# Breakout.net
KiCad netlist of a schematic drawn in Altium Designer
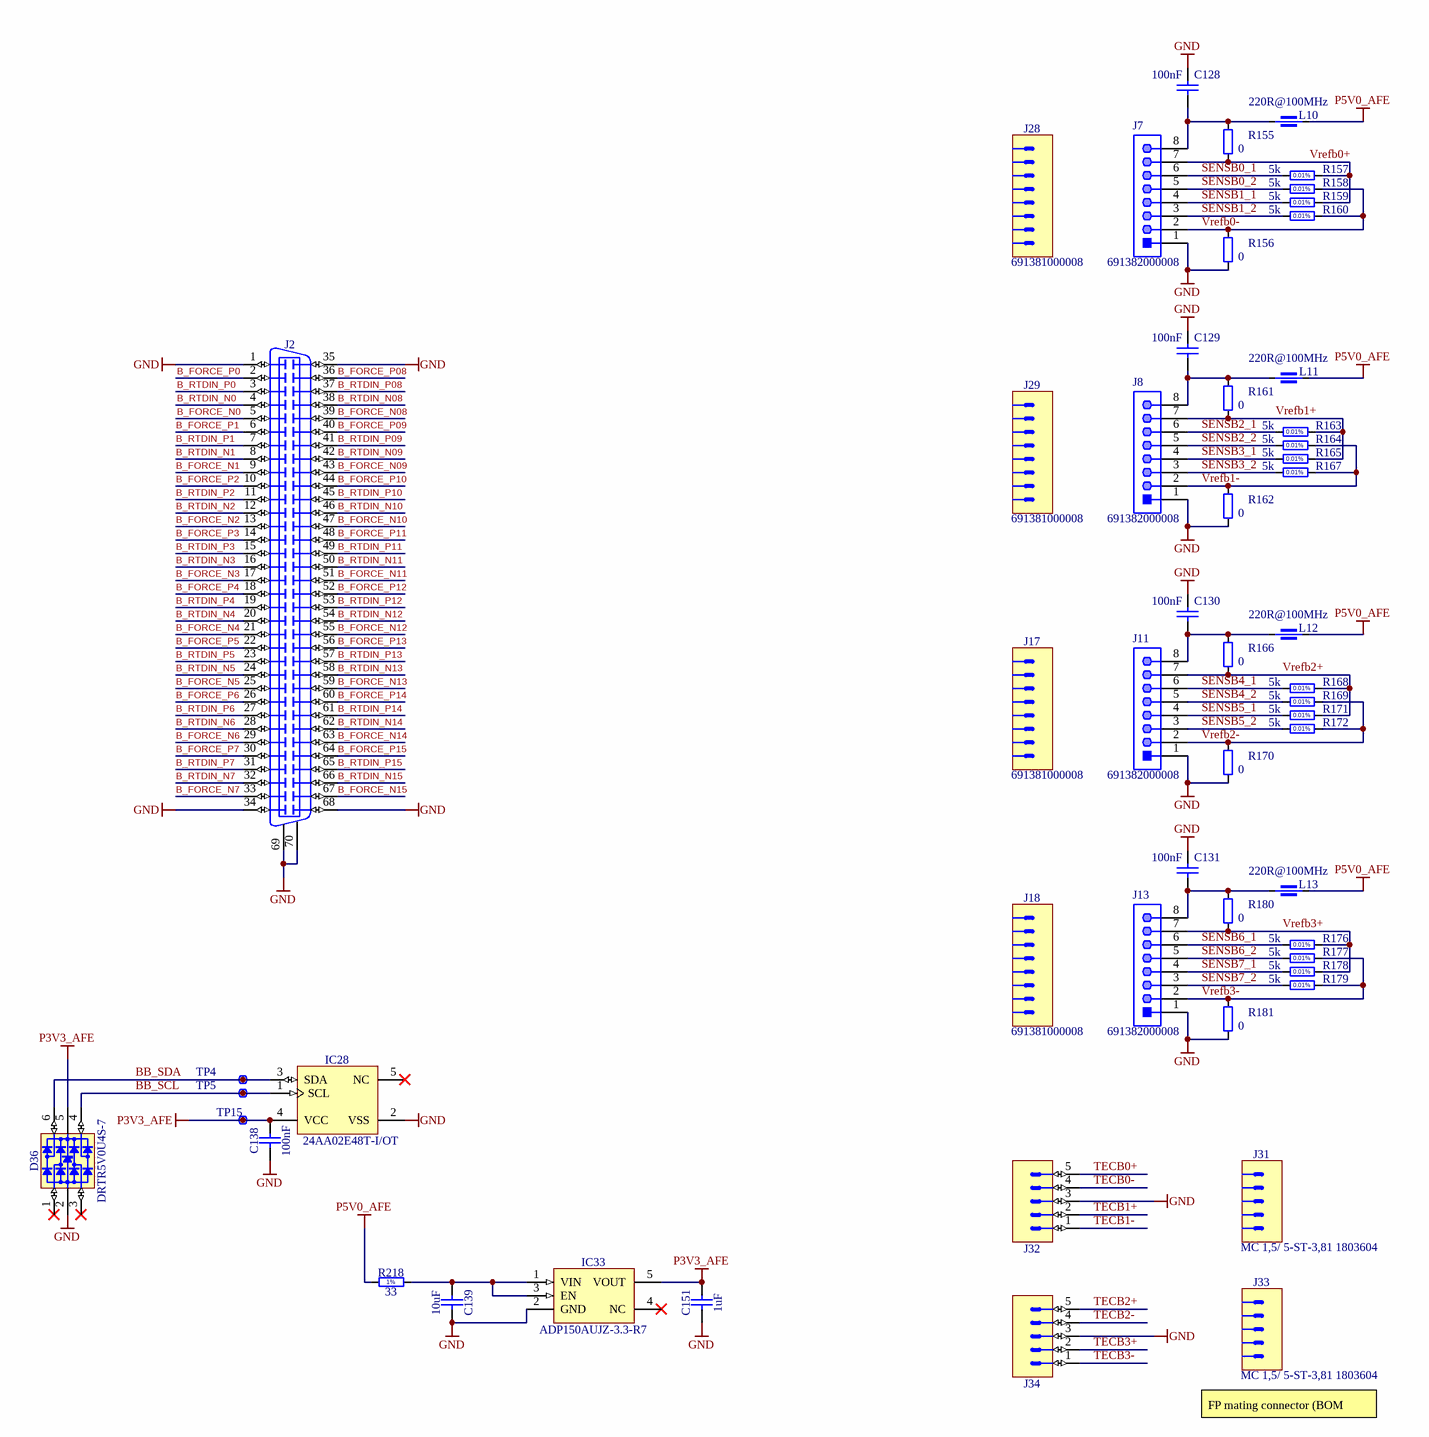
[diagram p0: Breakout.SchDoc]

(export (version "E")
  (design (tool "Eeschema 10.0.6"))
  (components
    (comp (ref "C128")
      (value "100nF")
      (footprint "CAPC1005X55N")
      (description "Non-polarised capacitor")
      (fields
        (field (name "PART NUMBER") "CC0402_100NF_16V_10%_X5R")
        (field (name "VOLTAGE") "16V")
        (field (name "AUTHOR") "CERN DEM JLC")
      )
      (libsource (lib "Capacitors") (part "Capacitor - non polarized"))
    )
    (comp (ref "C129")
      (value "100nF")
      (footprint "CAPC1005X55N")
      (description "Non-polarised capacitor")
      (fields
        (field (name "PART NUMBER") "CC0402_100NF_16V_10%_X5R")
        (field (name "VOLTAGE") "16V")
        (field (name "AUTHOR") "CERN DEM JLC")
      )
      (libsource (lib "Capacitors") (part "Capacitor - non polarized"))
    )
    (comp (ref "C130")
      (value "100nF")
      (footprint "CAPC1005X55N")
      (description "Non-polarised capacitor")
      (fields
        (field (name "PART NUMBER") "CC0402_100NF_16V_10%_X5R")
        (field (name "VOLTAGE") "16V")
        (field (name "AUTHOR") "CERN DEM JLC")
      )
      (libsource (lib "Capacitors") (part "Capacitor - non polarized"))
    )
    (comp (ref "C131")
      (value "100nF")
      (footprint "CAPC1005X55N")
      (description "Non-polarised capacitor")
      (fields
        (field (name "PART NUMBER") "CC0402_100NF_16V_10%_X5R")
        (field (name "VOLTAGE") "16V")
        (field (name "AUTHOR") "CERN DEM JLC")
      )
      (libsource (lib "Capacitors") (part "Capacitor - non polarized"))
    )
    (comp (ref "C138")
      (value "100nF")
      (footprint "CAPC1005X55N")
      (description "Non-polarised capacitor")
      (fields
        (field (name "PART NUMBER") "CC0402_100NF_16V_10%_X5R")
        (field (name "VOLTAGE") "16V")
        (field (name "AUTHOR") "CERN DEM JLC")
      )
      (libsource (lib "Capacitors") (part "Capacitor - non polarized"))
    )
    (comp (ref "C139")
      (value "10uF")
      (footprint "CAPC2012X135N")
      (description "Non-polarised capacitor")
      (fields
        (field (name "PART NUMBER") "CC0805_10UF_16V_10%_X5R")
        (field (name "VOLTAGE") "16V")
        (field (name "AUTHOR") "CERN DEM JLC")
      )
      (libsource (lib "Capacitors") (part "Capacitor - non polarized"))
    )
    (comp (ref "C151")
      (value "1uF")
      (footprint "CAPC1608X87N")
      (description "Non-polarised capacitor")
      (fields
        (field (name "PART NUMBER") "CC0603_1UF_25V_10%_X7R")
        (field (name "VOLTAGE") "25V")
        (field (name "AUTHOR") "CERN DEM JLC")
      )
      (libsource (lib "Capacitors") (part "Capacitor - non polarized"))
    )
    (comp (ref "D36")
      (value "DRTR5V0U4S-7")
      (footprint "SOT65P210X110-6N")
      (description "Integrated Quad Ultra-Low Capacitance ESD Protection")
      (fields (field (name "MANUFACTURER") "DIODES") (field (name "AUTHOR") "GK"))
      (libsource (lib "Diodes") (part "D_TVS_DRTR5V0U4S-7"))
    )
    (comp (ref "IC28")
      (value "24AA02E48T-I/OT")
      (footprint "SOT95P280X145-5N")
      (description "1.7V-5.5V, 2K I2C Serial EEPROM With EUI-48 Node Identity")
      (fields (field (name "MANUFACTURER") "MICROCHIP TECHNOLOGY") (field (name "AUTHOR") "CERN DEM MR"))
      (libsource (lib "ICs And Semiconductors") (part "24AA02E48T-I/OT"))
    )
    (comp (ref "IC33")
      (value "ADP150AUJZ-3.3-R7")
      (footprint "SOT95P280X90-5N")
      (description "Ultralow Noise, 150 mA CMOS Linear Regulator")
      (fields (field (name "MANUFACTURER") "ANALOG DEVICES") (field (name "AUTHOR") "CERN DEM JLC"))
      (libsource (lib "ICs And Semiconductors") (part "ADP150AUJZ"))
    )
    (comp (ref "J2")
      (value "DNP")
      (footprint "MOLEX_71430-0013")
      (description "Very High Density Cable Interconnect (VHDCI ) 68 Female")
      (fields
        (field (name "PART NUMBER") "MOLEX_71430-0013")
        (field (name "MANUFACTURER") "MOLEX")
        (field (name "AUTHOR") "CERN DEM JLC")
      )
      (libsource (lib "FMC_DIO_32ch_lvds_a") (part "MOLEX_71430-0013"))
    )
    (comp (ref "J7")
      (value "691382000008")
      (footprint "691382000008")
      (description "WR-TBL Serie 382 Vertical PCB Header, Pluggable, pitch 2.5mm, 8p")
      (fields (field (name "PUBLISHER") "Wurth Elektronik"))
      (libsource (lib "Altium_WR-TBL (rev19a)") (part "691382000008"))
    )
    (comp (ref "J8")
      (value "691382000008")
      (footprint "691382000008")
      (description "WR-TBL Serie 382 Vertical PCB Header, Pluggable, pitch 2.5mm, 8p")
      (fields (field (name "PUBLISHER") "Wurth Elektronik"))
      (libsource (lib "Altium_WR-TBL (rev19a)") (part "691382000008"))
    )
    (comp (ref "J11")
      (value "691382000008")
      (footprint "691382000008")
      (description "WR-TBL Serie 382 Vertical PCB Header, Pluggable, pitch 2.5mm, 8p")
      (fields (field (name "PUBLISHER") "Wurth Elektronik"))
      (libsource (lib "Altium_WR-TBL (rev19a)") (part "691382000008"))
    )
    (comp (ref "J13")
      (value "691382000008")
      (footprint "691382000008")
      (description "WR-TBL Serie 382 Vertical PCB Header, Pluggable, pitch 2.5mm, 8p")
      (fields (field (name "PUBLISHER") "Wurth Elektronik"))
      (libsource (lib "Altium_WR-TBL (rev19a)") (part "691382000008"))
    )
    (comp (ref "J17")
      (value "691381000008")
      (footprint "WURTH_691381000008")
      (description "Phoenix Contact 2.5 pitch terminal plug, 8 ways")
      (fields (field (name "MANUFACTURER") "WURTH") (field (name "MANUFACTURER PART NUMBER") "691381000008"))
      (libsource (lib "Connectors") (part "CON_TB_WURTH_691381000008"))
    )
    (comp (ref "J18")
      (value "691381000008")
      (footprint "WURTH_691381000008")
      (description "Phoenix Contact 2.5 pitch terminal plug, 8 ways")
      (fields (field (name "MANUFACTURER") "WURTH") (field (name "MANUFACTURER PART NUMBER") "691381000008"))
      (libsource (lib "Connectors") (part "CON_TB_WURTH_691381000008"))
    )
    (comp (ref "J28")
      (value "691381000008")
      (footprint "WURTH_691381000008")
      (description "Phoenix Contact 2.5 pitch terminal plug, 8 ways")
      (fields (field (name "MANUFACTURER") "WURTH") (field (name "MANUFACTURER PART NUMBER") "691381000008"))
      (libsource (lib "Connectors") (part "CON_TB_WURTH_691381000008"))
    )
    (comp (ref "J29")
      (value "691381000008")
      (footprint "WURTH_691381000008")
      (description "Phoenix Contact 2.5 pitch terminal plug, 8 ways")
      (fields (field (name "MANUFACTURER") "WURTH") (field (name "MANUFACTURER PART NUMBER") "691381000008"))
      (libsource (lib "Connectors") (part "CON_TB_WURTH_691381000008"))
    )
    (comp (ref "J31")
      (value "~")
      (footprint "PHOENIX_1803604")
      (description "Phoenix Contact 3.81 pitch terminal plug, 5 ways")
      (fields
        (field (name "MANUFACTURER") "Phoenix Contact")
        (field (name "MANUFACTURER PART NUMBER") "MC 1,5/ 5-ST-3,81 1803604")
      )
      (libsource (lib "Connectors") (part "PHOENIX_1803604"))
    )
    (comp (ref "J32")
      (value "~")
      (footprint "PHOENIX_1803455")
      (description "Connector 5 Male")
      (fields
        (field (name "PART NUMBER") "PHOENIX_1803455")
        (field (name "MANUFACTURER") "PHOENIX CONTACT")
        (field (name "AUTHOR") "CERN DEM JLC")
      )
      (libsource (lib "Connectors") (part "Connector 5 Male"))
    )
    (comp (ref "J33")
      (value "~")
      (footprint "PHOENIX_1803604")
      (description "Phoenix Contact 3.81 pitch terminal plug, 5 ways")
      (fields
        (field (name "MANUFACTURER") "Phoenix Contact")
        (field (name "MANUFACTURER PART NUMBER") "MC 1,5/ 5-ST-3,81 1803604")
      )
      (libsource (lib "Connectors") (part "PHOENIX_1803604"))
    )
    (comp (ref "J34")
      (value "~")
      (footprint "PHOENIX_1803455")
      (description "Connector 5 Male")
      (fields
        (field (name "PART NUMBER") "PHOENIX_1803455")
        (field (name "MANUFACTURER") "PHOENIX CONTACT")
        (field (name "AUTHOR") "CERN DEM JLC")
      )
      (libsource (lib "Connectors") (part "Connector 5 Male"))
    )
    (comp (ref "L10")
      (value "220R@100MHz")
      (footprint "INDC1005X55N")
      (fields
        (field (name "PART NUMBER") "IND0402_MURATA_BLM15HB221SN1")
        (field (name "POWER") "250mA")
        (field (name "TOLERANCE") "±25%")
        (field (name "AUTHOR") "CERN DEM JLC")
      )
      (libsource (lib "Inductors & Transformers") (part "Ferrite Bead"))
    )
    (comp (ref "L11")
      (value "220R@100MHz")
      (footprint "INDC1005X55N")
      (fields
        (field (name "PART NUMBER") "IND0402_MURATA_BLM15HB221SN1")
        (field (name "POWER") "250mA")
        (field (name "TOLERANCE") "±25%")
        (field (name "AUTHOR") "CERN DEM JLC")
      )
      (libsource (lib "Inductors & Transformers") (part "Ferrite Bead"))
    )
    (comp (ref "L12")
      (value "220R@100MHz")
      (footprint "INDC1005X55N")
      (fields
        (field (name "PART NUMBER") "IND0402_MURATA_BLM15HB221SN1")
        (field (name "POWER") "250mA")
        (field (name "TOLERANCE") "±25%")
        (field (name "AUTHOR") "CERN DEM JLC")
      )
      (libsource (lib "Inductors & Transformers") (part "Ferrite Bead"))
    )
    (comp (ref "L13")
      (value "220R@100MHz")
      (footprint "INDC1005X55N")
      (fields
        (field (name "PART NUMBER") "IND0402_MURATA_BLM15HB221SN1")
        (field (name "POWER") "250mA")
        (field (name "TOLERANCE") "±25%")
        (field (name "AUTHOR") "CERN DEM JLC")
      )
      (libsource (lib "Inductors & Transformers") (part "Ferrite Bead"))
    )
    (comp (ref "R155")
      (value "0")
      (footprint "RESC1608X55N")
      (description "Resistor")
      (fields
        (field (name "PART NUMBER") "R0603_0R_JUMPER")
        (field (name "MANUFACTURER") "GENERIC")
        (field (name "AUTHOR") "CERN DEM JLC")
      )
      (libsource (lib "Resistors") (part "Resistor"))
    )
    (comp (ref "R156")
      (value "0")
      (footprint "RESC1608X55N")
      (description "Resistor")
      (fields
        (field (name "PART NUMBER") "R0603_0R_JUMPER")
        (field (name "MANUFACTURER") "GENERIC")
        (field (name "AUTHOR") "CERN DEM JLC")
      )
      (libsource (lib "Resistors") (part "Resistor"))
    )
    (comp (ref "R157")
      (value "5k")
      (footprint "RESC2013X64N")
      (description "Resistor - 0.01%")
      (fields
        (field (name "PART NUMBER") "R0805_5K_0.01%_0.2W_0.2PPM_VISHAY_VSMP")
        (field (name "POWER") "0.2W")
        (field (name "AUTHOR") "CERN DEM JLC")
      )
      (libsource (lib "Resistors") (part "Resistor - 0.01%"))
    )
    (comp (ref "R158")
      (value "5k")
      (footprint "RESC2013X64N")
      (description "Resistor - 0.01%")
      (fields
        (field (name "PART NUMBER") "R0805_5K_0.01%_0.2W_0.2PPM_VISHAY_VSMP")
        (field (name "POWER") "0.2W")
        (field (name "AUTHOR") "CERN DEM JLC")
      )
      (libsource (lib "Resistors") (part "Resistor - 0.01%"))
    )
    (comp (ref "R159")
      (value "5k")
      (footprint "RESC2013X64N")
      (description "Resistor - 0.01%")
      (fields
        (field (name "PART NUMBER") "R0805_5K_0.01%_0.2W_0.2PPM_VISHAY_VSMP")
        (field (name "POWER") "0.2W")
        (field (name "AUTHOR") "CERN DEM JLC")
      )
      (libsource (lib "Resistors") (part "Resistor - 0.01%"))
    )
    (comp (ref "R160")
      (value "5k")
      (footprint "RESC2013X64N")
      (description "Resistor - 0.01%")
      (fields
        (field (name "PART NUMBER") "R0805_5K_0.01%_0.2W_0.2PPM_VISHAY_VSMP")
        (field (name "POWER") "0.2W")
        (field (name "AUTHOR") "CERN DEM JLC")
      )
      (libsource (lib "Resistors") (part "Resistor - 0.01%"))
    )
    (comp (ref "R161")
      (value "0")
      (footprint "RESC1608X55N")
      (description "Resistor")
      (fields
        (field (name "PART NUMBER") "R0603_0R_JUMPER")
        (field (name "MANUFACTURER") "GENERIC")
        (field (name "AUTHOR") "CERN DEM JLC")
      )
      (libsource (lib "Resistors") (part "Resistor"))
    )
    (comp (ref "R162")
      (value "0")
      (footprint "RESC1608X55N")
      (description "Resistor")
      (fields
        (field (name "PART NUMBER") "R0603_0R_JUMPER")
        (field (name "MANUFACTURER") "GENERIC")
        (field (name "AUTHOR") "CERN DEM JLC")
      )
      (libsource (lib "Resistors") (part "Resistor"))
    )
    (comp (ref "R163")
      (value "5k")
      (footprint "RESC2013X64N")
      (description "Resistor - 0.01%")
      (fields
        (field (name "PART NUMBER") "R0805_5K_0.01%_0.2W_0.2PPM_VISHAY_VSMP")
        (field (name "POWER") "0.2W")
        (field (name "AUTHOR") "CERN DEM JLC")
      )
      (libsource (lib "Resistors") (part "Resistor - 0.01%"))
    )
    (comp (ref "R164")
      (value "5k")
      (footprint "RESC2013X64N")
      (description "Resistor - 0.01%")
      (fields
        (field (name "PART NUMBER") "R0805_5K_0.01%_0.2W_0.2PPM_VISHAY_VSMP")
        (field (name "POWER") "0.2W")
        (field (name "AUTHOR") "CERN DEM JLC")
      )
      (libsource (lib "Resistors") (part "Resistor - 0.01%"))
    )
    (comp (ref "R165")
      (value "5k")
      (footprint "RESC2013X64N")
      (description "Resistor - 0.01%")
      (fields
        (field (name "PART NUMBER") "R0805_5K_0.01%_0.2W_0.2PPM_VISHAY_VSMP")
        (field (name "POWER") "0.2W")
        (field (name "AUTHOR") "CERN DEM JLC")
      )
      (libsource (lib "Resistors") (part "Resistor - 0.01%"))
    )
    (comp (ref "R166")
      (value "0")
      (footprint "RESC1608X55N")
      (description "Resistor")
      (fields
        (field (name "PART NUMBER") "R0603_0R_JUMPER")
        (field (name "MANUFACTURER") "GENERIC")
        (field (name "AUTHOR") "CERN DEM JLC")
      )
      (libsource (lib "Resistors") (part "Resistor"))
    )
    (comp (ref "R167")
      (value "5k")
      (footprint "RESC2013X64N")
      (description "Resistor - 0.01%")
      (fields
        (field (name "PART NUMBER") "R0805_5K_0.01%_0.2W_0.2PPM_VISHAY_VSMP")
        (field (name "POWER") "0.2W")
        (field (name "AUTHOR") "CERN DEM JLC")
      )
      (libsource (lib "Resistors") (part "Resistor - 0.01%"))
    )
    (comp (ref "R168")
      (value "5k")
      (footprint "RESC2013X64N")
      (description "Resistor - 0.01%")
      (fields
        (field (name "PART NUMBER") "R0805_5K_0.01%_0.2W_0.2PPM_VISHAY_VSMP")
        (field (name "POWER") "0.2W")
        (field (name "AUTHOR") "CERN DEM JLC")
      )
      (libsource (lib "Resistors") (part "Resistor - 0.01%"))
    )
    (comp (ref "R169")
      (value "5k")
      (footprint "RESC2013X64N")
      (description "Resistor - 0.01%")
      (fields
        (field (name "PART NUMBER") "R0805_5K_0.01%_0.2W_0.2PPM_VISHAY_VSMP")
        (field (name "POWER") "0.2W")
        (field (name "AUTHOR") "CERN DEM JLC")
      )
      (libsource (lib "Resistors") (part "Resistor - 0.01%"))
    )
    (comp (ref "R170")
      (value "0")
      (footprint "RESC1608X55N")
      (description "Resistor")
      (fields
        (field (name "PART NUMBER") "R0603_0R_JUMPER")
        (field (name "MANUFACTURER") "GENERIC")
        (field (name "AUTHOR") "CERN DEM JLC")
      )
      (libsource (lib "Resistors") (part "Resistor"))
    )
    (comp (ref "R171")
      (value "5k")
      (footprint "RESC2013X64N")
      (description "Resistor - 0.01%")
      (fields
        (field (name "PART NUMBER") "R0805_5K_0.01%_0.2W_0.2PPM_VISHAY_VSMP")
        (field (name "POWER") "0.2W")
        (field (name "AUTHOR") "CERN DEM JLC")
      )
      (libsource (lib "Resistors") (part "Resistor - 0.01%"))
    )
    (comp (ref "R172")
      (value "5k")
      (footprint "RESC2013X64N")
      (description "Resistor - 0.01%")
      (fields
        (field (name "PART NUMBER") "R0805_5K_0.01%_0.2W_0.2PPM_VISHAY_VSMP")
        (field (name "POWER") "0.2W")
        (field (name "AUTHOR") "CERN DEM JLC")
      )
      (libsource (lib "Resistors") (part "Resistor - 0.01%"))
    )
    (comp (ref "R176")
      (value "5k")
      (footprint "RESC2013X64N")
      (description "Resistor - 0.01%")
      (fields
        (field (name "PART NUMBER") "R0805_5K_0.01%_0.2W_0.2PPM_VISHAY_VSMP")
        (field (name "POWER") "0.2W")
        (field (name "AUTHOR") "CERN DEM JLC")
      )
      (libsource (lib "Resistors") (part "Resistor - 0.01%"))
    )
    (comp (ref "R177")
      (value "5k")
      (footprint "RESC2013X64N")
      (description "Resistor - 0.01%")
      (fields
        (field (name "PART NUMBER") "R0805_5K_0.01%_0.2W_0.2PPM_VISHAY_VSMP")
        (field (name "POWER") "0.2W")
        (field (name "AUTHOR") "CERN DEM JLC")
      )
      (libsource (lib "Resistors") (part "Resistor - 0.01%"))
    )
    (comp (ref "R178")
      (value "5k")
      (footprint "RESC2013X64N")
      (description "Resistor - 0.01%")
      (fields
        (field (name "PART NUMBER") "R0805_5K_0.01%_0.2W_0.2PPM_VISHAY_VSMP")
        (field (name "POWER") "0.2W")
        (field (name "AUTHOR") "CERN DEM JLC")
      )
      (libsource (lib "Resistors") (part "Resistor - 0.01%"))
    )
    (comp (ref "R179")
      (value "5k")
      (footprint "RESC2013X64N")
      (description "Resistor - 0.01%")
      (fields
        (field (name "PART NUMBER") "R0805_5K_0.01%_0.2W_0.2PPM_VISHAY_VSMP")
        (field (name "POWER") "0.2W")
        (field (name "AUTHOR") "CERN DEM JLC")
      )
      (libsource (lib "Resistors") (part "Resistor - 0.01%"))
    )
    (comp (ref "R180")
      (value "0")
      (footprint "RESC1608X55N")
      (description "Resistor")
      (fields
        (field (name "PART NUMBER") "R0603_0R_JUMPER")
        (field (name "MANUFACTURER") "GENERIC")
        (field (name "AUTHOR") "CERN DEM JLC")
      )
      (libsource (lib "Resistors") (part "Resistor"))
    )
    (comp (ref "R181")
      (value "0")
      (footprint "RESC1608X55N")
      (description "Resistor")
      (fields
        (field (name "PART NUMBER") "R0603_0R_JUMPER")
        (field (name "MANUFACTURER") "GENERIC")
        (field (name "AUTHOR") "CERN DEM JLC")
      )
      (libsource (lib "Resistors") (part "Resistor"))
    )
    (comp (ref "R218")
      (value "33")
      (footprint "RESC1005X40N")
      (description "Resistor - 1%")
      (fields
        (field (name "PART NUMBER") "R0402_33R_1%_0.0625W_100PPM")
        (field (name "POWER") "0.0625W")
        (field (name "AUTHOR") "CERN DEM JLC")
      )
      (libsource (lib "Resistors") (part "Resistor - 1%"))
    )
    (comp (ref "TP4")
      (value "Test Point")
      (footprint "TPS127")
      (fields (field (name "PART NUMBER") "SMD_PAD_1.27X1.27MM") (field (name "AUTHOR") "CERN DEM JLC"))
      (libsource (lib "Eletro-mechanical") (part "Test Point"))
    )
    (comp (ref "TP5")
      (value "Test Point")
      (footprint "TPS127")
      (fields (field (name "PART NUMBER") "SMD_PAD_1.27X1.27MM") (field (name "AUTHOR") "CERN DEM JLC"))
      (libsource (lib "Eletro-mechanical") (part "Test Point"))
    )
    (comp (ref "TP15")
      (value "Test Point")
      (footprint "TPS127")
      (fields (field (name "PART NUMBER") "SMD_PAD_1.27X1.27MM") (field (name "AUTHOR") "CERN DEM JLC"))
      (libsource (lib "Eletro-mechanical") (part "Test Point"))
    )
  )
  (nets
    (net (code "1") (name "/BB_SCL") (class "Default")
      (node (ref "D36") (pin "4") (pinfunction "I/O3_4") (pintype "bidirectional"))
      (node (ref "IC28") (pin "1") (pinfunction "SCL_1") (pintype "input"))
      (node (ref "TP5") (pin "1") (pinfunction "1_1") (pintype "bidirectional"))
    )
    (net (code "2") (name "/BB_SDA") (class "Default")
      (node (ref "D36") (pin "6") (pinfunction "I/O4_6") (pintype "bidirectional"))
      (node (ref "IC28") (pin "3") (pinfunction "SDA_3") (pintype "bidirectional"))
      (node (ref "TP4") (pin "1") (pinfunction "1_1") (pintype "bidirectional"))
    )
    (net (code "3") (name "/B_FORCE_N0") (class "Default")
      (node (ref "J2") (pin "5") (pinfunction "5_5") (pintype "bidirectional"))
    )
    (net (code "4") (name "/B_FORCE_N1") (class "Default")
      (node (ref "J2") (pin "9") (pinfunction "9_9") (pintype "bidirectional"))
    )
    (net (code "5") (name "/B_FORCE_N2") (class "Default")
      (node (ref "J2") (pin "13") (pinfunction "13_13") (pintype "bidirectional"))
    )
    (net (code "6") (name "/B_FORCE_N3") (class "Default")
      (node (ref "J2") (pin "17") (pinfunction "17_17") (pintype "bidirectional"))
    )
    (net (code "7") (name "/B_FORCE_N4") (class "Default")
      (node (ref "J2") (pin "21") (pinfunction "21_21") (pintype "bidirectional"))
    )
    (net (code "8") (name "/B_FORCE_N5") (class "Default")
      (node (ref "J2") (pin "25") (pinfunction "25_25") (pintype "bidirectional"))
    )
    (net (code "9") (name "/B_FORCE_N6") (class "Default")
      (node (ref "J2") (pin "29") (pinfunction "29_29") (pintype "bidirectional"))
    )
    (net (code "10") (name "/B_FORCE_N7") (class "Default")
      (node (ref "J2") (pin "33") (pinfunction "33_33") (pintype "bidirectional"))
    )
    (net (code "11") (name "/B_FORCE_N08") (class "Default")
      (node (ref "J2") (pin "39") (pinfunction "39_39") (pintype "bidirectional"))
    )
    (net (code "12") (name "/B_FORCE_N09") (class "Default")
      (node (ref "J2") (pin "43") (pinfunction "43_43") (pintype "bidirectional"))
    )
    (net (code "13") (name "/B_FORCE_N10") (class "Default")
      (node (ref "J2") (pin "47") (pinfunction "47_47") (pintype "bidirectional"))
    )
    (net (code "14") (name "/B_FORCE_N11") (class "Default")
      (node (ref "J2") (pin "51") (pinfunction "51_51") (pintype "bidirectional"))
    )
    (net (code "15") (name "/B_FORCE_N12") (class "Default")
      (node (ref "J2") (pin "55") (pinfunction "55_55") (pintype "bidirectional"))
    )
    (net (code "16") (name "/B_FORCE_N13") (class "Default")
      (node (ref "J2") (pin "59") (pinfunction "59_59") (pintype "bidirectional"))
    )
    (net (code "17") (name "/B_FORCE_N14") (class "Default")
      (node (ref "J2") (pin "63") (pinfunction "63_63") (pintype "bidirectional"))
    )
    (net (code "18") (name "/B_FORCE_N15") (class "Default")
      (node (ref "J2") (pin "67") (pinfunction "67_67") (pintype "bidirectional"))
    )
    (net (code "19") (name "/B_FORCE_P0") (class "Default")
      (node (ref "J2") (pin "2") (pinfunction "2_2") (pintype "bidirectional"))
    )
    (net (code "20") (name "/B_FORCE_P1") (class "Default")
      (node (ref "J2") (pin "6") (pinfunction "6_6") (pintype "bidirectional"))
    )
    (net (code "21") (name "/B_FORCE_P2") (class "Default")
      (node (ref "J2") (pin "10") (pinfunction "10_10") (pintype "bidirectional"))
    )
    (net (code "22") (name "/B_FORCE_P3") (class "Default")
      (node (ref "J2") (pin "14") (pinfunction "14_14") (pintype "bidirectional"))
    )
    (net (code "23") (name "/B_FORCE_P4") (class "Default")
      (node (ref "J2") (pin "18") (pinfunction "18_18") (pintype "bidirectional"))
    )
    (net (code "24") (name "/B_FORCE_P5") (class "Default")
      (node (ref "J2") (pin "22") (pinfunction "22_22") (pintype "bidirectional"))
    )
    (net (code "25") (name "/B_FORCE_P6") (class "Default")
      (node (ref "J2") (pin "26") (pinfunction "26_26") (pintype "bidirectional"))
    )
    (net (code "26") (name "/B_FORCE_P7") (class "Default")
      (node (ref "J2") (pin "30") (pinfunction "30_30") (pintype "bidirectional"))
    )
    (net (code "27") (name "/B_FORCE_P08") (class "Default")
      (node (ref "J2") (pin "36") (pinfunction "36_36") (pintype "bidirectional"))
    )
    (net (code "28") (name "/B_FORCE_P09") (class "Default")
      (node (ref "J2") (pin "40") (pinfunction "40_40") (pintype "bidirectional"))
    )
    (net (code "29") (name "/B_FORCE_P10") (class "Default")
      (node (ref "J2") (pin "44") (pinfunction "44_44") (pintype "bidirectional"))
    )
    (net (code "30") (name "/B_FORCE_P11") (class "Default")
      (node (ref "J2") (pin "48") (pinfunction "48_48") (pintype "bidirectional"))
    )
    (net (code "31") (name "/B_FORCE_P12") (class "Default")
      (node (ref "J2") (pin "52") (pinfunction "52_52") (pintype "bidirectional"))
    )
    (net (code "32") (name "/B_FORCE_P13") (class "Default")
      (node (ref "J2") (pin "56") (pinfunction "56_56") (pintype "bidirectional"))
    )
    (net (code "33") (name "/B_FORCE_P14") (class "Default")
      (node (ref "J2") (pin "60") (pinfunction "60_60") (pintype "bidirectional"))
    )
    (net (code "34") (name "/B_FORCE_P15") (class "Default")
      (node (ref "J2") (pin "64") (pinfunction "64_64") (pintype "bidirectional"))
    )
    (net (code "35") (name "/B_RTDIN_N0") (class "Default")
      (node (ref "J2") (pin "4") (pinfunction "4_4") (pintype "bidirectional"))
    )
    (net (code "36") (name "/B_RTDIN_N1") (class "Default")
      (node (ref "J2") (pin "8") (pinfunction "8_8") (pintype "bidirectional"))
    )
    (net (code "37") (name "/B_RTDIN_N2") (class "Default")
      (node (ref "J2") (pin "12") (pinfunction "12_12") (pintype "bidirectional"))
    )
    (net (code "38") (name "/B_RTDIN_N3") (class "Default")
      (node (ref "J2") (pin "16") (pinfunction "16_16") (pintype "bidirectional"))
    )
    (net (code "39") (name "/B_RTDIN_N4") (class "Default")
      (node (ref "J2") (pin "20") (pinfunction "20_20") (pintype "bidirectional"))
    )
    (net (code "40") (name "/B_RTDIN_N5") (class "Default")
      (node (ref "J2") (pin "24") (pinfunction "24_24") (pintype "bidirectional"))
    )
    (net (code "41") (name "/B_RTDIN_N6") (class "Default")
      (node (ref "J2") (pin "28") (pinfunction "28_28") (pintype "bidirectional"))
    )
    (net (code "42") (name "/B_RTDIN_N7") (class "Default")
      (node (ref "J2") (pin "32") (pinfunction "32_32") (pintype "bidirectional"))
    )
    (net (code "43") (name "/B_RTDIN_N08") (class "Default")
      (node (ref "J2") (pin "38") (pinfunction "38_38") (pintype "bidirectional"))
    )
    (net (code "44") (name "/B_RTDIN_N09") (class "Default")
      (node (ref "J2") (pin "42") (pinfunction "42_42") (pintype "bidirectional"))
    )
    (net (code "45") (name "/B_RTDIN_N10") (class "Default")
      (node (ref "J2") (pin "46") (pinfunction "46_46") (pintype "bidirectional"))
    )
    (net (code "46") (name "/B_RTDIN_N11") (class "Default")
      (node (ref "J2") (pin "50") (pinfunction "50_50") (pintype "bidirectional"))
    )
    (net (code "47") (name "/B_RTDIN_N12") (class "Default")
      (node (ref "J2") (pin "54") (pinfunction "54_54") (pintype "bidirectional"))
    )
    (net (code "48") (name "/B_RTDIN_N13") (class "Default")
      (node (ref "J2") (pin "58") (pinfunction "58_58") (pintype "bidirectional"))
    )
    (net (code "49") (name "/B_RTDIN_N14") (class "Default")
      (node (ref "J2") (pin "62") (pinfunction "62_62") (pintype "bidirectional"))
    )
    (net (code "50") (name "/B_RTDIN_N15") (class "Default")
      (node (ref "J2") (pin "66") (pinfunction "66_66") (pintype "bidirectional"))
    )
    (net (code "51") (name "/B_RTDIN_P0") (class "Default")
      (node (ref "J2") (pin "3") (pinfunction "3_3") (pintype "bidirectional"))
    )
    (net (code "52") (name "/B_RTDIN_P1") (class "Default")
      (node (ref "J2") (pin "7") (pinfunction "7_7") (pintype "bidirectional"))
    )
    (net (code "53") (name "/B_RTDIN_P2") (class "Default")
      (node (ref "J2") (pin "11") (pinfunction "11_11") (pintype "bidirectional"))
    )
    (net (code "54") (name "/B_RTDIN_P3") (class "Default")
      (node (ref "J2") (pin "15") (pinfunction "15_15") (pintype "bidirectional"))
    )
    (net (code "55") (name "/B_RTDIN_P4") (class "Default")
      (node (ref "J2") (pin "19") (pinfunction "19_19") (pintype "bidirectional"))
    )
    (net (code "56") (name "/B_RTDIN_P5") (class "Default")
      (node (ref "J2") (pin "23") (pinfunction "23_23") (pintype "bidirectional"))
    )
    (net (code "57") (name "/B_RTDIN_P6") (class "Default")
      (node (ref "J2") (pin "27") (pinfunction "27_27") (pintype "bidirectional"))
    )
    (net (code "58") (name "/B_RTDIN_P7") (class "Default")
      (node (ref "J2") (pin "31") (pinfunction "31_31") (pintype "bidirectional"))
    )
    (net (code "59") (name "/B_RTDIN_P08") (class "Default")
      (node (ref "J2") (pin "37") (pinfunction "37_37") (pintype "bidirectional"))
    )
    (net (code "60") (name "/B_RTDIN_P09") (class "Default")
      (node (ref "J2") (pin "41") (pinfunction "41_41") (pintype "bidirectional"))
    )
    (net (code "61") (name "/B_RTDIN_P10") (class "Default")
      (node (ref "J2") (pin "45") (pinfunction "45_45") (pintype "bidirectional"))
    )
    (net (code "62") (name "/B_RTDIN_P11") (class "Default")
      (node (ref "J2") (pin "49") (pinfunction "49_49") (pintype "bidirectional"))
    )
    (net (code "63") (name "/B_RTDIN_P12") (class "Default")
      (node (ref "J2") (pin "53") (pinfunction "53_53") (pintype "bidirectional"))
    )
    (net (code "64") (name "/B_RTDIN_P13") (class "Default")
      (node (ref "J2") (pin "57") (pinfunction "57_57") (pintype "bidirectional"))
    )
    (net (code "65") (name "/B_RTDIN_P14") (class "Default")
      (node (ref "J2") (pin "61") (pinfunction "61_61") (pintype "bidirectional"))
    )
    (net (code "66") (name "/B_RTDIN_P15") (class "Default")
      (node (ref "J2") (pin "65") (pinfunction "65_65") (pintype "bidirectional"))
    )
    (net (code "67") (name "/SENSB0_1") (class "Default")
      (node (ref "J7") (pin "6") (pinfunction "6_6") (pintype "passive"))
      (node (ref "R157") (pin "1") (pinfunction "1_1") (pintype "passive"))
    )
    (net (code "68") (name "/SENSB0_2") (class "Default")
      (node (ref "J7") (pin "5") (pinfunction "5_5") (pintype "passive"))
      (node (ref "R158") (pin "1") (pinfunction "1_1") (pintype "passive"))
    )
    (net (code "69") (name "/SENSB1_1") (class "Default")
      (node (ref "J7") (pin "4") (pinfunction "4_4") (pintype "passive"))
      (node (ref "R159") (pin "1") (pinfunction "1_1") (pintype "passive"))
    )
    (net (code "70") (name "/SENSB1_2") (class "Default")
      (node (ref "J7") (pin "3") (pinfunction "3_3") (pintype "passive"))
      (node (ref "R160") (pin "1") (pinfunction "1_1") (pintype "passive"))
    )
    (net (code "71") (name "/SENSB2_1") (class "Default")
      (node (ref "J8") (pin "6") (pinfunction "6_6") (pintype "passive"))
      (node (ref "R163") (pin "1") (pinfunction "1_1") (pintype "passive"))
    )
    (net (code "72") (name "/SENSB2_2") (class "Default")
      (node (ref "J8") (pin "5") (pinfunction "5_5") (pintype "passive"))
      (node (ref "R164") (pin "1") (pinfunction "1_1") (pintype "passive"))
    )
    (net (code "73") (name "/SENSB3_1") (class "Default")
      (node (ref "J8") (pin "4") (pinfunction "4_4") (pintype "passive"))
      (node (ref "R165") (pin "1") (pinfunction "1_1") (pintype "passive"))
    )
    (net (code "74") (name "/SENSB3_2") (class "Default")
      (node (ref "J8") (pin "3") (pinfunction "3_3") (pintype "passive"))
      (node (ref "R167") (pin "1") (pinfunction "1_1") (pintype "passive"))
    )
    (net (code "75") (name "/SENSB4_1") (class "Default")
      (node (ref "J11") (pin "6") (pinfunction "6_6") (pintype "passive"))
      (node (ref "R168") (pin "1") (pinfunction "1_1") (pintype "passive"))
    )
    (net (code "76") (name "/SENSB4_2") (class "Default")
      (node (ref "J11") (pin "5") (pinfunction "5_5") (pintype "passive"))
      (node (ref "R169") (pin "1") (pinfunction "1_1") (pintype "passive"))
    )
    (net (code "77") (name "/SENSB5_1") (class "Default")
      (node (ref "J11") (pin "4") (pinfunction "4_4") (pintype "passive"))
      (node (ref "R171") (pin "1") (pinfunction "1_1") (pintype "passive"))
    )
    (net (code "78") (name "/SENSB5_2") (class "Default")
      (node (ref "J11") (pin "3") (pinfunction "3_3") (pintype "passive"))
      (node (ref "R172") (pin "1") (pinfunction "1_1") (pintype "passive"))
    )
    (net (code "79") (name "/SENSB6_1") (class "Default")
      (node (ref "J13") (pin "6") (pinfunction "6_6") (pintype "passive"))
      (node (ref "R176") (pin "1") (pinfunction "1_1") (pintype "passive"))
    )
    (net (code "80") (name "/SENSB6_2") (class "Default")
      (node (ref "J13") (pin "5") (pinfunction "5_5") (pintype "passive"))
      (node (ref "R177") (pin "1") (pinfunction "1_1") (pintype "passive"))
    )
    (net (code "81") (name "/SENSB7_1") (class "Default")
      (node (ref "J13") (pin "4") (pinfunction "4_4") (pintype "passive"))
      (node (ref "R178") (pin "1") (pinfunction "1_1") (pintype "passive"))
    )
    (net (code "82") (name "/SENSB7_2") (class "Default")
      (node (ref "J13") (pin "3") (pinfunction "3_3") (pintype "passive"))
      (node (ref "R179") (pin "1") (pinfunction "1_1") (pintype "passive"))
    )
    (net (code "83") (name "/TECB0+") (class "Default")
      (node (ref "J32") (pin "5") (pinfunction "5_5") (pintype "bidirectional"))
    )
    (net (code "84") (name "/TECB0-") (class "Default")
      (node (ref "J32") (pin "4") (pinfunction "4_4") (pintype "bidirectional"))
    )
    (net (code "85") (name "/TECB1+") (class "Default")
      (node (ref "J32") (pin "2") (pinfunction "2_2") (pintype "bidirectional"))
    )
    (net (code "86") (name "/TECB1-") (class "Default")
      (node (ref "J32") (pin "1") (pinfunction "1_1") (pintype "bidirectional"))
    )
    (net (code "87") (name "/TECB2+") (class "Default")
      (node (ref "J34") (pin "5") (pinfunction "5_5") (pintype "bidirectional"))
    )
    (net (code "88") (name "/TECB2-") (class "Default")
      (node (ref "J34") (pin "4") (pinfunction "4_4") (pintype "bidirectional"))
    )
    (net (code "89") (name "/TECB3+") (class "Default")
      (node (ref "J34") (pin "2") (pinfunction "2_2") (pintype "bidirectional"))
    )
    (net (code "90") (name "/TECB3-") (class "Default")
      (node (ref "J34") (pin "1") (pinfunction "1_1") (pintype "bidirectional"))
    )
    (net (code "91") (name "/Vrefb0+") (class "Default")
      (node (ref "J7") (pin "7") (pinfunction "7_7") (pintype "passive"))
      (node (ref "R155") (pin "1") (pinfunction "1_1") (pintype "passive"))
      (node (ref "R157") (pin "2") (pinfunction "2_2") (pintype "passive"))
      (node (ref "R159") (pin "2") (pinfunction "2_2") (pintype "passive"))
    )
    (net (code "92") (name "/Vrefb0-") (class "Default")
      (node (ref "J7") (pin "2") (pinfunction "2_2") (pintype "passive"))
      (node (ref "R156") (pin "2") (pinfunction "2_2") (pintype "passive"))
      (node (ref "R158") (pin "2") (pinfunction "2_2") (pintype "passive"))
      (node (ref "R160") (pin "2") (pinfunction "2_2") (pintype "passive"))
    )
    (net (code "93") (name "/Vrefb1+") (class "Default")
      (node (ref "J8") (pin "7") (pinfunction "7_7") (pintype "passive"))
      (node (ref "R161") (pin "1") (pinfunction "1_1") (pintype "passive"))
      (node (ref "R163") (pin "2") (pinfunction "2_2") (pintype "passive"))
      (node (ref "R165") (pin "2") (pinfunction "2_2") (pintype "passive"))
    )
    (net (code "94") (name "/Vrefb1-") (class "Default")
      (node (ref "J8") (pin "2") (pinfunction "2_2") (pintype "passive"))
      (node (ref "R162") (pin "2") (pinfunction "2_2") (pintype "passive"))
      (node (ref "R164") (pin "2") (pinfunction "2_2") (pintype "passive"))
      (node (ref "R167") (pin "2") (pinfunction "2_2") (pintype "passive"))
    )
    (net (code "95") (name "/Vrefb2+") (class "Default")
      (node (ref "J11") (pin "7") (pinfunction "7_7") (pintype "passive"))
      (node (ref "R166") (pin "1") (pinfunction "1_1") (pintype "passive"))
      (node (ref "R168") (pin "2") (pinfunction "2_2") (pintype "passive"))
      (node (ref "R171") (pin "2") (pinfunction "2_2") (pintype "passive"))
    )
    (net (code "96") (name "/Vrefb2-") (class "Default")
      (node (ref "J11") (pin "2") (pinfunction "2_2") (pintype "passive"))
      (node (ref "R169") (pin "2") (pinfunction "2_2") (pintype "passive"))
      (node (ref "R170") (pin "2") (pinfunction "2_2") (pintype "passive"))
      (node (ref "R172") (pin "2") (pinfunction "2_2") (pintype "passive"))
    )
    (net (code "97") (name "/Vrefb3+") (class "Default")
      (node (ref "J13") (pin "7") (pinfunction "7_7") (pintype "passive"))
      (node (ref "R176") (pin "2") (pinfunction "2_2") (pintype "passive"))
      (node (ref "R178") (pin "2") (pinfunction "2_2") (pintype "passive"))
      (node (ref "R180") (pin "1") (pinfunction "1_1") (pintype "passive"))
    )
    (net (code "98") (name "/Vrefb3-") (class "Default")
      (node (ref "J13") (pin "2") (pinfunction "2_2") (pintype "passive"))
      (node (ref "R177") (pin "2") (pinfunction "2_2") (pintype "passive"))
      (node (ref "R179") (pin "2") (pinfunction "2_2") (pintype "passive"))
      (node (ref "R181") (pin "2") (pinfunction "2_2") (pintype "passive"))
    )
    (net (code "99") (name "GND") (class "Default")
      (node (ref "C128") (pin "1") (pinfunction "1_1") (pintype "passive"))
      (node (ref "C129") (pin "1") (pinfunction "1_1") (pintype "passive"))
      (node (ref "C130") (pin "1") (pinfunction "1_1") (pintype "passive"))
      (node (ref "C131") (pin "1") (pinfunction "1_1") (pintype "passive"))
      (node (ref "C138") (pin "1") (pinfunction "1_1") (pintype "passive"))
      (node (ref "C139") (pin "2") (pinfunction "2_2") (pintype "passive"))
      (node (ref "C151") (pin "1") (pinfunction "1_1") (pintype "passive"))
      (node (ref "D36") (pin "2") (pinfunction "GND_2") (pintype "power_in"))
      (node (ref "IC28") (pin "2") (pinfunction "VSS_2") (pintype "power_in"))
      (node (ref "IC33") (pin "2") (pinfunction "GND_2") (pintype "power_in"))
      (node (ref "J11") (pin "1") (pinfunction "1_1") (pintype "passive"))
      (node (ref "J13") (pin "1") (pinfunction "1_1") (pintype "passive"))
      (node (ref "J2") (pin "1") (pinfunction "1_1") (pintype "bidirectional"))
      (node (ref "J2") (pin "34") (pinfunction "34_34") (pintype "bidirectional"))
      (node (ref "J2") (pin "35") (pinfunction "35_35") (pintype "bidirectional"))
      (node (ref "J2") (pin "68") (pinfunction "68_68") (pintype "bidirectional"))
      (node (ref "J2") (pin "69") (pinfunction "69_69") (pintype "passive"))
      (node (ref "J2") (pin "70") (pinfunction "70_70") (pintype "passive"))
      (node (ref "J32") (pin "3") (pinfunction "3_3") (pintype "bidirectional"))
      (node (ref "J34") (pin "3") (pinfunction "3_3") (pintype "bidirectional"))
      (node (ref "J7") (pin "1") (pinfunction "1_1") (pintype "passive"))
      (node (ref "J8") (pin "1") (pinfunction "1_1") (pintype "passive"))
      (node (ref "R156") (pin "1") (pinfunction "1_1") (pintype "passive"))
      (node (ref "R162") (pin "1") (pinfunction "1_1") (pintype "passive"))
      (node (ref "R170") (pin "1") (pinfunction "1_1") (pintype "passive"))
      (node (ref "R181") (pin "1") (pinfunction "1_1") (pintype "passive"))
    )
    (net (code "100") (name "Net-(C128-Pad2)") (class "Default")
      (node (ref "C128") (pin "2") (pinfunction "2_2") (pintype "passive"))
      (node (ref "J7") (pin "8") (pinfunction "8_8") (pintype "passive"))
      (node (ref "L10") (pin "1") (pinfunction "1_1") (pintype "passive"))
      (node (ref "R155") (pin "2") (pinfunction "2_2") (pintype "passive"))
    )
    (net (code "101") (name "Net-(C129-Pad2)") (class "Default")
      (node (ref "C129") (pin "2") (pinfunction "2_2") (pintype "passive"))
      (node (ref "J8") (pin "8") (pinfunction "8_8") (pintype "passive"))
      (node (ref "L11") (pin "1") (pinfunction "1_1") (pintype "passive"))
      (node (ref "R161") (pin "2") (pinfunction "2_2") (pintype "passive"))
    )
    (net (code "102") (name "Net-(C130-Pad2)") (class "Default")
      (node (ref "C130") (pin "2") (pinfunction "2_2") (pintype "passive"))
      (node (ref "J11") (pin "8") (pinfunction "8_8") (pintype "passive"))
      (node (ref "L12") (pin "1") (pinfunction "1_1") (pintype "passive"))
      (node (ref "R166") (pin "2") (pinfunction "2_2") (pintype "passive"))
    )
    (net (code "103") (name "Net-(C131-Pad2)") (class "Default")
      (node (ref "C131") (pin "2") (pinfunction "2_2") (pintype "passive"))
      (node (ref "J13") (pin "8") (pinfunction "8_8") (pintype "passive"))
      (node (ref "L13") (pin "1") (pinfunction "1_1") (pintype "passive"))
      (node (ref "R180") (pin "2") (pinfunction "2_2") (pintype "passive"))
    )
    (net (code "104") (name "Net-(IC33-EN)") (class "Default")
      (node (ref "C139") (pin "1") (pinfunction "1_1") (pintype "passive"))
      (node (ref "IC33") (pin "1") (pinfunction "VIN_1") (pintype "input"))
      (node (ref "IC33") (pin "3") (pinfunction "EN_3") (pintype "input"))
      (node (ref "R218") (pin "2") (pinfunction "2_2") (pintype "passive"))
    )
    (net (code "105") (name "P3V3_AFE") (class "Default")
      (node (ref "C138") (pin "2") (pinfunction "2_2") (pintype "passive"))
      (node (ref "C151") (pin "2") (pinfunction "2_2") (pintype "passive"))
      (node (ref "D36") (pin "5") (pinfunction "VBUS_5") (pintype "power_in"))
      (node (ref "IC28") (pin "4") (pinfunction "VCC_4") (pintype "power_in"))
      (node (ref "IC33") (pin "5") (pinfunction "VOUT_5") (pintype "power_in"))
      (node (ref "TP15") (pin "1") (pinfunction "1_1") (pintype "bidirectional"))
    )
    (net (code "106") (name "P5V0_AFE") (class "Default")
      (node (ref "L10") (pin "2") (pinfunction "2_2") (pintype "passive"))
      (node (ref "L11") (pin "2") (pinfunction "2_2") (pintype "passive"))
      (node (ref "L12") (pin "2") (pinfunction "2_2") (pintype "passive"))
      (node (ref "L13") (pin "2") (pinfunction "2_2") (pintype "passive"))
      (node (ref "R218") (pin "1") (pinfunction "1_1") (pintype "passive"))
    )
    (net (code "107") (name "unconnected-(D36-I{slash}O1-Pad1)") (class "Default")
      (node (ref "D36") (pin "1") (pinfunction "I/O1_1") (pintype "bidirectional+no_connect"))
    )
    (net (code "108") (name "unconnected-(D36-I{slash}O2-Pad3)") (class "Default")
      (node (ref "D36") (pin "3") (pinfunction "I/O2_3") (pintype "bidirectional+no_connect"))
    )
    (net (code "109") (name "unconnected-(IC28-NC-Pad5)") (class "Default")
      (node (ref "IC28") (pin "5") (pinfunction "NC_5") (pintype "passive+no_connect"))
    )
    (net (code "110") (name "unconnected-(IC33-NC-Pad4)") (class "Default")
      (node (ref "IC33") (pin "4") (pinfunction "NC_4") (pintype "passive+no_connect"))
    )
  )
)
